# Nano_Jtag.net
KiCad netlist of a schematic drawn in Altium Designer
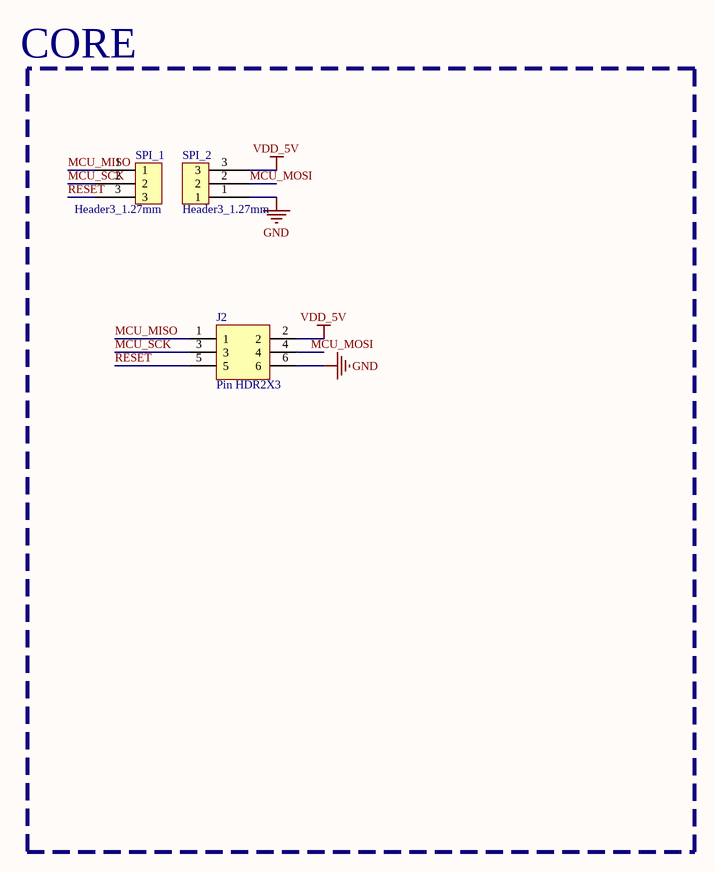
[diagram p0: Nano_Jtag.SchDoc]

(export (version "E")
  (design (tool "Eeschema 10.0.6"))
  (components
    (comp (ref "J2")
      (value "Pin HDR2X3")
      (footprint "Pin HDR2X3/2.54mm-S")
      (libsource (lib "排针") (part "Pin HDR2X3"))
    )
    (comp (ref "SPI_1")
      (value "Header3_1.27mm")
      (footprint "HEADER3_1.27mm")
      (libsource (lib "未分类IC") (part "Header3_1.27mm"))
    )
    (comp (ref "SPI_2")
      (value "Header3_1.27mm")
      (footprint "HEADER3_1.27mm")
      (libsource (lib "") (part "Header3_1.27mm_1"))
    )
  )
  (nets
    (net (code "1") (name "/MCU_MISO") (class "Default")
      (node (ref "J2") (pin "1") (pinfunction "1_1") (pintype "passive"))
      (node (ref "SPI_1") (pin "1") (pinfunction "1_1") (pintype "passive"))
    )
    (net (code "2") (name "/MCU_MOSI") (class "Default")
      (node (ref "J2") (pin "4") (pinfunction "4_4") (pintype "passive"))
      (node (ref "SPI_2") (pin "2") (pinfunction "2_2") (pintype "passive"))
    )
    (net (code "3") (name "/MCU_SCK") (class "Default")
      (node (ref "J2") (pin "3") (pinfunction "3_3") (pintype "passive"))
      (node (ref "SPI_1") (pin "2") (pinfunction "2_2") (pintype "passive"))
    )
    (net (code "4") (name "/RESET") (class "Default")
      (node (ref "J2") (pin "5") (pinfunction "5_5") (pintype "passive"))
      (node (ref "SPI_1") (pin "3") (pinfunction "3_3") (pintype "passive"))
    )
    (net (code "5") (name "GND") (class "Default")
      (node (ref "J2") (pin "6") (pinfunction "6_6") (pintype "passive"))
      (node (ref "SPI_2") (pin "1") (pinfunction "1_1") (pintype "passive"))
    )
    (net (code "6") (name "VDD_5V") (class "Default")
      (node (ref "J2") (pin "2") (pinfunction "2_2") (pintype "passive"))
      (node (ref "SPI_2") (pin "3") (pinfunction "3_3") (pintype "passive"))
    )
  )
)
